# hv_io_main_connector.net
KiCad netlist of a schematic drawn in Altium Designer
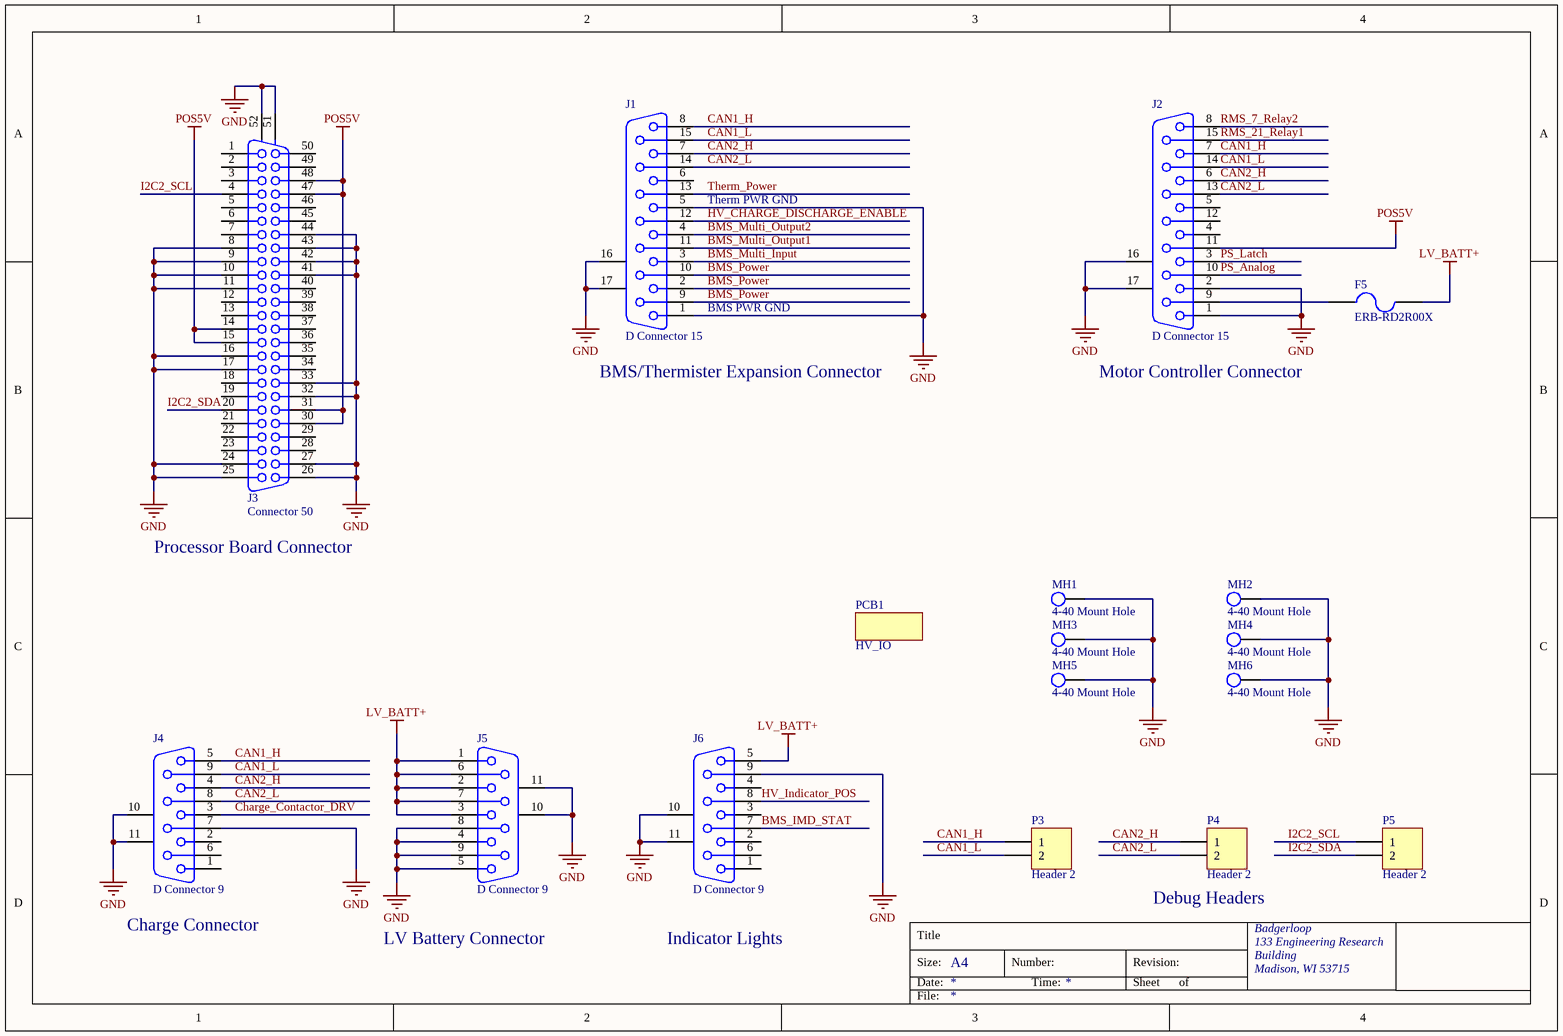
[diagram p0: hv_io_main_connector.SchDoc]

(export (version "E")
  (design (tool "Eeschema 10.0.6"))
  (components
    (comp (ref "F5")
      (value "ERB-RD2R00X")
      (footprint "SMD-0402-RES")
      (description "FUSE BOARD MOUNT 2A 32VDC 0402")
      (fields (field (name "MANUFACTURER") "Panasonic"))
      (libsource (lib "temp") (part "ERB-RD2R00X"))
    )
    (comp (ref "J1")
      (value "D Connector 15")
      (footprint "DSUB1.385-2H15")
      (description "Receptacle Assembly, 15 Position, Right Angle")
      (fields (field (name "PUBLISHER") "Altium Limited"))
      (libsource (lib "connector") (part "D Connector 15"))
    )
    (comp (ref "J2")
      (value "D Connector 15")
      (footprint "DSUB1.385-2H15")
      (description "Receptacle Assembly, 15 Position, Right Angle")
      (fields (field (name "PUBLISHER") "Altium Limited"))
      (libsource (lib "connector") (part "D Connector 15"))
    )
    (comp (ref "J3")
      (value "Connector 50")
      (footprint "050DSUB1.27-H96")
      (description "Plug Header Assembly")
      (fields (field (name "MANUFACTURER") "HARTING"))
      (libsource (lib "shelby_temp") (part "Connector 50"))
    )
    (comp (ref "J4")
      (value "D Connector 9")
      (footprint "DSUB1.385-2H9")
      (description "Receptacle Assembly, 9 Position, Right Angle")
      (fields (field (name "PUBLISHER") "Altium Limited"))
      (libsource (lib "connector") (part "D Connector 9"))
    )
    (comp (ref "J5")
      (value "D Connector 9")
      (footprint "DSUB1.385-2H9")
      (description "Receptacle Assembly, 9 Position, Right Angle")
      (fields (field (name "PUBLISHER") "Altium Limited"))
      (libsource (lib "connector") (part "D Connector 9"))
    )
    (comp (ref "J6")
      (value "D Connector 9")
      (footprint "DSUB1.385-2H9")
      (description "Receptacle Assembly, 9 Position, Right Angle")
      (fields (field (name "PUBLISHER") "Altium Limited"))
      (libsource (lib "connector") (part "D Connector 9"))
    )
    (comp (ref "MH1")
      (value "4-40 Mount Hole")
      (footprint "MH")
      (libsource (lib "misc") (part "4-40 Mount Hole"))
    )
    (comp (ref "MH2")
      (value "4-40 Mount Hole")
      (footprint "MH")
      (libsource (lib "misc") (part "4-40 Mount Hole"))
    )
    (comp (ref "MH3")
      (value "4-40 Mount Hole")
      (footprint "MH")
      (libsource (lib "misc") (part "4-40 Mount Hole"))
    )
    (comp (ref "MH4")
      (value "4-40 Mount Hole")
      (footprint "MH")
      (libsource (lib "misc") (part "4-40 Mount Hole"))
    )
    (comp (ref "MH5")
      (value "4-40 Mount Hole")
      (footprint "MH")
      (libsource (lib "misc") (part "4-40 Mount Hole"))
    )
    (comp (ref "MH6")
      (value "4-40 Mount Hole")
      (footprint "MH")
      (libsource (lib "misc") (part "4-40 Mount Hole"))
    )
    (comp (ref "P3")
      (value "Header 2")
      (footprint "Pin Header 1x2 TH Pitch 2.54mm")
      (description "Header, 2-Pin")
      (fields (field (name "PUBLISHER") "Altium Limited"))
      (libsource (lib "connector") (part "Header 2"))
    )
    (comp (ref "P4")
      (value "Header 2")
      (footprint "Pin Header 1x2 TH Pitch 2.54mm")
      (description "Header, 2-Pin")
      (fields (field (name "PUBLISHER") "Altium Limited"))
      (libsource (lib "connector") (part "Header 2"))
    )
    (comp (ref "P5")
      (value "Header 2")
      (footprint "Pin Header 1x2 TH Pitch 2.54mm")
      (description "Header, 2-Pin")
      (fields (field (name "PUBLISHER") "Altium Limited"))
      (libsource (lib "connector") (part "Header 2"))
    )
    (comp (ref "PCB1") (value "HV_IO") (footprint "PCB") (libsource (lib "temp") (part "PCB")))
  )
  (nets
    (net (code "1") (name "/BMS_IMD_STAT") (class "Default")
      (node (ref "J6") (pin "7") (pinfunction "7_7") (pintype "passive"))
    )
    (net (code "2") (name "/BMS_Multi_Input") (class "Default")
      (node (ref "J1") (pin "3") (pinfunction "3_3") (pintype "passive"))
    )
    (net (code "3") (name "/BMS_Multi_Output1") (class "Default")
      (node (ref "J1") (pin "11") (pinfunction "11_11") (pintype "passive"))
    )
    (net (code "4") (name "/BMS_Multi_Output2") (class "Default")
      (node (ref "J1") (pin "4") (pinfunction "4_4") (pintype "passive"))
    )
    (net (code "5") (name "/BMS_Power") (class "Default")
      (node (ref "J1") (pin "10") (pinfunction "10_10") (pintype "passive"))
      (node (ref "J1") (pin "2") (pinfunction "2_2") (pintype "passive"))
      (node (ref "J1") (pin "9") (pinfunction "9_9") (pintype "passive"))
    )
    (net (code "6") (name "/CAN1_H") (class "Default")
      (node (ref "J1") (pin "8") (pinfunction "8_8") (pintype "passive"))
      (node (ref "J2") (pin "7") (pinfunction "7_7") (pintype "passive"))
      (node (ref "J4") (pin "5") (pinfunction "5_5") (pintype "passive"))
      (node (ref "P3") (pin "1") (pinfunction "1_1") (pintype "passive"))
    )
    (net (code "7") (name "/CAN1_L") (class "Default")
      (node (ref "J1") (pin "15") (pinfunction "15_15") (pintype "passive"))
      (node (ref "J2") (pin "14") (pinfunction "14_14") (pintype "passive"))
      (node (ref "J4") (pin "9") (pinfunction "9_9") (pintype "passive"))
      (node (ref "P3") (pin "2") (pinfunction "2_2") (pintype "passive"))
    )
    (net (code "8") (name "/CAN2_H") (class "Default")
      (node (ref "J1") (pin "7") (pinfunction "7_7") (pintype "passive"))
      (node (ref "J2") (pin "6") (pinfunction "6_6") (pintype "passive"))
      (node (ref "J4") (pin "4") (pinfunction "4_4") (pintype "passive"))
      (node (ref "P4") (pin "1") (pinfunction "1_1") (pintype "passive"))
    )
    (net (code "9") (name "/CAN2_L") (class "Default")
      (node (ref "J1") (pin "14") (pinfunction "14_14") (pintype "passive"))
      (node (ref "J2") (pin "13") (pinfunction "13_13") (pintype "passive"))
      (node (ref "J4") (pin "8") (pinfunction "8_8") (pintype "passive"))
      (node (ref "P4") (pin "2") (pinfunction "2_2") (pintype "passive"))
    )
    (net (code "10") (name "/Charge_Contactor_DRV") (class "Default")
      (node (ref "J4") (pin "3") (pinfunction "3_3") (pintype "passive"))
    )
    (net (code "11") (name "/HV_CHARGE_DISCHARGE_ENABLE") (class "Default")
      (node (ref "J1") (pin "12") (pinfunction "12_12") (pintype "passive"))
    )
    (net (code "12") (name "/HV_Indicator_POS") (class "Default")
      (node (ref "J6") (pin "8") (pinfunction "8_8") (pintype "passive"))
    )
    (net (code "13") (name "/I2C2_SCL") (class "Default")
      (node (ref "J3") (pin "4") (pinfunction "4_4") (pintype "passive"))
      (node (ref "P5") (pin "1") (pinfunction "1_1") (pintype "passive"))
    )
    (net (code "14") (name "/I2C2_SDA") (class "Default")
      (node (ref "J3") (pin "20") (pinfunction "20_20") (pintype "passive"))
      (node (ref "P5") (pin "2") (pinfunction "2_2") (pintype "passive"))
    )
    (net (code "15") (name "/PS_Analog") (class "Default")
      (node (ref "J2") (pin "10") (pinfunction "10_10") (pintype "passive"))
    )
    (net (code "16") (name "/PS_Latch") (class "Default")
      (node (ref "J2") (pin "3") (pinfunction "3_3") (pintype "passive"))
    )
    (net (code "17") (name "/RMS_7_Relay2") (class "Default")
      (node (ref "J2") (pin "8") (pinfunction "8_8") (pintype "passive"))
    )
    (net (code "18") (name "/RMS_21_Relay1") (class "Default")
      (node (ref "J2") (pin "15") (pinfunction "15_15") (pintype "passive"))
    )
    (net (code "19") (name "/Therm_Power") (class "Default")
      (node (ref "J1") (pin "13") (pinfunction "13_13") (pintype "passive"))
    )
    (net (code "20") (name "GND") (class "Default")
      (node (ref "J1") (pin "1") (pinfunction "1_1") (pintype "passive"))
      (node (ref "J1") (pin "16") (pinfunction "MH1_16") (pintype "passive"))
      (node (ref "J1") (pin "17") (pinfunction "MH2_17") (pintype "passive"))
      (node (ref "J1") (pin "5") (pinfunction "5_5") (pintype "passive"))
      (node (ref "J2") (pin "1") (pinfunction "1_1") (pintype "passive"))
      (node (ref "J2") (pin "16") (pinfunction "MH1_16") (pintype "passive"))
      (node (ref "J2") (pin "17") (pinfunction "MH2_17") (pintype "passive"))
      (node (ref "J2") (pin "2") (pinfunction "2_2") (pintype "passive"))
      (node (ref "J3") (pin "10") (pinfunction "10_10") (pintype "passive"))
      (node (ref "J3") (pin "11") (pinfunction "11_11") (pintype "passive"))
      (node (ref "J3") (pin "16") (pinfunction "16_16") (pintype "passive"))
      (node (ref "J3") (pin "17") (pinfunction "17_17") (pintype "passive"))
      (node (ref "J3") (pin "24") (pinfunction "24_24") (pintype "passive"))
      (node (ref "J3") (pin "25") (pinfunction "25_25") (pintype "passive"))
      (node (ref "J3") (pin "26") (pinfunction "26_26") (pintype "passive"))
      (node (ref "J3") (pin "27") (pinfunction "27_27") (pintype "passive"))
      (node (ref "J3") (pin "32") (pinfunction "32_32") (pintype "passive"))
      (node (ref "J3") (pin "33") (pinfunction "33_33") (pintype "passive"))
      (node (ref "J3") (pin "41") (pinfunction "41_41") (pintype "passive"))
      (node (ref "J3") (pin "42") (pinfunction "42_42") (pintype "passive"))
      (node (ref "J3") (pin "43") (pinfunction "43_43") (pintype "passive"))
      (node (ref "J3") (pin "44") (pinfunction "44_44") (pintype "passive"))
      (node (ref "J3") (pin "51") (pinfunction "51_51") (pintype "passive"))
      (node (ref "J3") (pin "52") (pinfunction "52_52") (pintype "passive"))
      (node (ref "J3") (pin "8") (pinfunction "8_8") (pintype "passive"))
      (node (ref "J3") (pin "9") (pinfunction "9_9") (pintype "passive"))
      (node (ref "J4") (pin "10") (pinfunction "MH1_10") (pintype "passive"))
      (node (ref "J4") (pin "11") (pinfunction "MH2_11") (pintype "passive"))
      (node (ref "J4") (pin "7") (pinfunction "7_7") (pintype "passive"))
      (node (ref "J5") (pin "10") (pinfunction "MH1_10") (pintype "passive"))
      (node (ref "J5") (pin "11") (pinfunction "MH2_11") (pintype "passive"))
      (node (ref "J5") (pin "4") (pinfunction "4_4") (pintype "passive"))
      (node (ref "J5") (pin "5") (pinfunction "5_5") (pintype "passive"))
      (node (ref "J5") (pin "8") (pinfunction "8_8") (pintype "passive"))
      (node (ref "J5") (pin "9") (pinfunction "9_9") (pintype "passive"))
      (node (ref "J6") (pin "10") (pinfunction "MH1_10") (pintype "passive"))
      (node (ref "J6") (pin "11") (pinfunction "MH2_11") (pintype "passive"))
      (node (ref "J6") (pin "9") (pinfunction "9_9") (pintype "passive"))
      (node (ref "MH1") (pin "46") (pinfunction "46_46") (pintype "passive"))
      (node (ref "MH2") (pin "46") (pinfunction "46_46") (pintype "passive"))
      (node (ref "MH3") (pin "46") (pinfunction "46_46") (pintype "passive"))
      (node (ref "MH4") (pin "46") (pinfunction "46_46") (pintype "passive"))
      (node (ref "MH5") (pin "46") (pinfunction "46_46") (pintype "passive"))
      (node (ref "MH6") (pin "46") (pinfunction "46_46") (pintype "passive"))
    )
    (net (code "21") (name "LV_BATT+") (class "Default")
      (node (ref "F5") (pin "2") (pinfunction "2_2") (pintype "passive"))
      (node (ref "J5") (pin "1") (pinfunction "1_1") (pintype "passive"))
      (node (ref "J5") (pin "2") (pinfunction "2_2") (pintype "passive"))
      (node (ref "J5") (pin "3") (pinfunction "3_3") (pintype "passive"))
      (node (ref "J5") (pin "6") (pinfunction "6_6") (pintype "passive"))
      (node (ref "J5") (pin "7") (pinfunction "7_7") (pintype "passive"))
      (node (ref "J6") (pin "5") (pinfunction "5_5") (pintype "passive"))
    )
    (net (code "22") (name "Net-(F5-Pad1)") (class "Default")
      (node (ref "F5") (pin "1") (pinfunction "1_1") (pintype "passive"))
      (node (ref "J2") (pin "9") (pinfunction "9_9") (pintype "passive"))
    )
    (net (code "23") (name "POS5V") (class "Default")
      (node (ref "J2") (pin "11") (pinfunction "11_11") (pintype "passive"))
      (node (ref "J3") (pin "14") (pinfunction "14_14") (pintype "passive"))
      (node (ref "J3") (pin "15") (pinfunction "15_15") (pintype "passive"))
      (node (ref "J3") (pin "30") (pinfunction "30_30") (pintype "passive"))
      (node (ref "J3") (pin "31") (pinfunction "31_31") (pintype "passive"))
      (node (ref "J3") (pin "47") (pinfunction "47_47") (pintype "passive"))
      (node (ref "J3") (pin "48") (pinfunction "48_48") (pintype "passive"))
    )
    (net (code "24") (name "unconnected-(J1-Pad6)") (class "Default")
      (node (ref "J1") (pin "6") (pinfunction "6_6") (pintype "passive"))
    )
    (net (code "25") (name "unconnected-(J2-Pad4)") (class "Default")
      (node (ref "J2") (pin "4") (pinfunction "4_4") (pintype "passive"))
    )
    (net (code "26") (name "unconnected-(J2-Pad5)") (class "Default")
      (node (ref "J2") (pin "5") (pinfunction "5_5") (pintype "passive"))
    )
    (net (code "27") (name "unconnected-(J2-Pad12)") (class "Default")
      (node (ref "J2") (pin "12") (pinfunction "12_12") (pintype "passive"))
    )
    (net (code "28") (name "unconnected-(J3-Pad1)") (class "Default")
      (node (ref "J3") (pin "1") (pinfunction "1_1") (pintype "passive"))
    )
    (net (code "29") (name "unconnected-(J3-Pad2)") (class "Default")
      (node (ref "J3") (pin "2") (pinfunction "2_2") (pintype "passive"))
    )
    (net (code "30") (name "unconnected-(J3-Pad3)") (class "Default")
      (node (ref "J3") (pin "3") (pinfunction "3_3") (pintype "passive"))
    )
    (net (code "31") (name "unconnected-(J3-Pad5)") (class "Default")
      (node (ref "J3") (pin "5") (pinfunction "5_5") (pintype "passive"))
    )
    (net (code "32") (name "unconnected-(J3-Pad6)") (class "Default")
      (node (ref "J3") (pin "6") (pinfunction "6_6") (pintype "passive"))
    )
    (net (code "33") (name "unconnected-(J3-Pad7)") (class "Default")
      (node (ref "J3") (pin "7") (pinfunction "7_7") (pintype "passive"))
    )
    (net (code "34") (name "unconnected-(J3-Pad12)") (class "Default")
      (node (ref "J3") (pin "12") (pinfunction "12_12") (pintype "passive"))
    )
    (net (code "35") (name "unconnected-(J3-Pad13)") (class "Default")
      (node (ref "J3") (pin "13") (pinfunction "13_13") (pintype "passive"))
    )
    (net (code "36") (name "unconnected-(J3-Pad18)") (class "Default")
      (node (ref "J3") (pin "18") (pinfunction "18_18") (pintype "passive"))
    )
    (net (code "37") (name "unconnected-(J3-Pad19)") (class "Default")
      (node (ref "J3") (pin "19") (pinfunction "19_19") (pintype "passive"))
    )
    (net (code "38") (name "unconnected-(J3-Pad21)") (class "Default")
      (node (ref "J3") (pin "21") (pinfunction "21_21") (pintype "passive"))
    )
    (net (code "39") (name "unconnected-(J3-Pad22)") (class "Default")
      (node (ref "J3") (pin "22") (pinfunction "22_22") (pintype "passive"))
    )
    (net (code "40") (name "unconnected-(J3-Pad23)") (class "Default")
      (node (ref "J3") (pin "23") (pinfunction "23_23") (pintype "passive"))
    )
    (net (code "41") (name "unconnected-(J3-Pad28)") (class "Default")
      (node (ref "J3") (pin "28") (pinfunction "28_28") (pintype "passive"))
    )
    (net (code "42") (name "unconnected-(J3-Pad29)") (class "Default")
      (node (ref "J3") (pin "29") (pinfunction "29_29") (pintype "passive"))
    )
    (net (code "43") (name "unconnected-(J3-Pad34)") (class "Default")
      (node (ref "J3") (pin "34") (pinfunction "34_34") (pintype "passive"))
    )
    (net (code "44") (name "unconnected-(J3-Pad35)") (class "Default")
      (node (ref "J3") (pin "35") (pinfunction "35_35") (pintype "passive"))
    )
    (net (code "45") (name "unconnected-(J3-Pad36)") (class "Default")
      (node (ref "J3") (pin "36") (pinfunction "36_36") (pintype "passive"))
    )
    (net (code "46") (name "unconnected-(J3-Pad37)") (class "Default")
      (node (ref "J3") (pin "37") (pinfunction "37_37") (pintype "passive"))
    )
    (net (code "47") (name "unconnected-(J3-Pad38)") (class "Default")
      (node (ref "J3") (pin "38") (pinfunction "38_38") (pintype "passive"))
    )
    (net (code "48") (name "unconnected-(J3-Pad39)") (class "Default")
      (node (ref "J3") (pin "39") (pinfunction "39_39") (pintype "passive"))
    )
    (net (code "49") (name "unconnected-(J3-Pad40)") (class "Default")
      (node (ref "J3") (pin "40") (pinfunction "40_40") (pintype "passive"))
    )
    (net (code "50") (name "unconnected-(J3-Pad45)") (class "Default")
      (node (ref "J3") (pin "45") (pinfunction "45_45") (pintype "passive"))
    )
    (net (code "51") (name "unconnected-(J3-Pad46)") (class "Default")
      (node (ref "J3") (pin "46") (pinfunction "46_46") (pintype "passive"))
    )
    (net (code "52") (name "unconnected-(J3-Pad49)") (class "Default")
      (node (ref "J3") (pin "49") (pinfunction "49_49") (pintype "passive"))
    )
    (net (code "53") (name "unconnected-(J3-Pad50)") (class "Default")
      (node (ref "J3") (pin "50") (pinfunction "50_50") (pintype "passive"))
    )
    (net (code "54") (name "unconnected-(J4-Pad1)") (class "Default")
      (node (ref "J4") (pin "1") (pinfunction "1_1") (pintype "passive"))
    )
    (net (code "55") (name "unconnected-(J4-Pad2)") (class "Default")
      (node (ref "J4") (pin "2") (pinfunction "2_2") (pintype "passive"))
    )
    (net (code "56") (name "unconnected-(J4-Pad6)") (class "Default")
      (node (ref "J4") (pin "6") (pinfunction "6_6") (pintype "passive"))
    )
    (net (code "57") (name "unconnected-(J6-Pad1)") (class "Default")
      (node (ref "J6") (pin "1") (pinfunction "1_1") (pintype "passive"))
    )
    (net (code "58") (name "unconnected-(J6-Pad2)") (class "Default")
      (node (ref "J6") (pin "2") (pinfunction "2_2") (pintype "passive"))
    )
    (net (code "59") (name "unconnected-(J6-Pad3)") (class "Default")
      (node (ref "J6") (pin "3") (pinfunction "3_3") (pintype "passive"))
    )
    (net (code "60") (name "unconnected-(J6-Pad4)") (class "Default")
      (node (ref "J6") (pin "4") (pinfunction "4_4") (pintype "passive"))
    )
    (net (code "61") (name "unconnected-(J6-Pad6)") (class "Default")
      (node (ref "J6") (pin "6") (pinfunction "6_6") (pintype "passive"))
    )
  )
)
